# BMS_Communications.net
KiCad netlist of a schematic drawn in Altium Designer
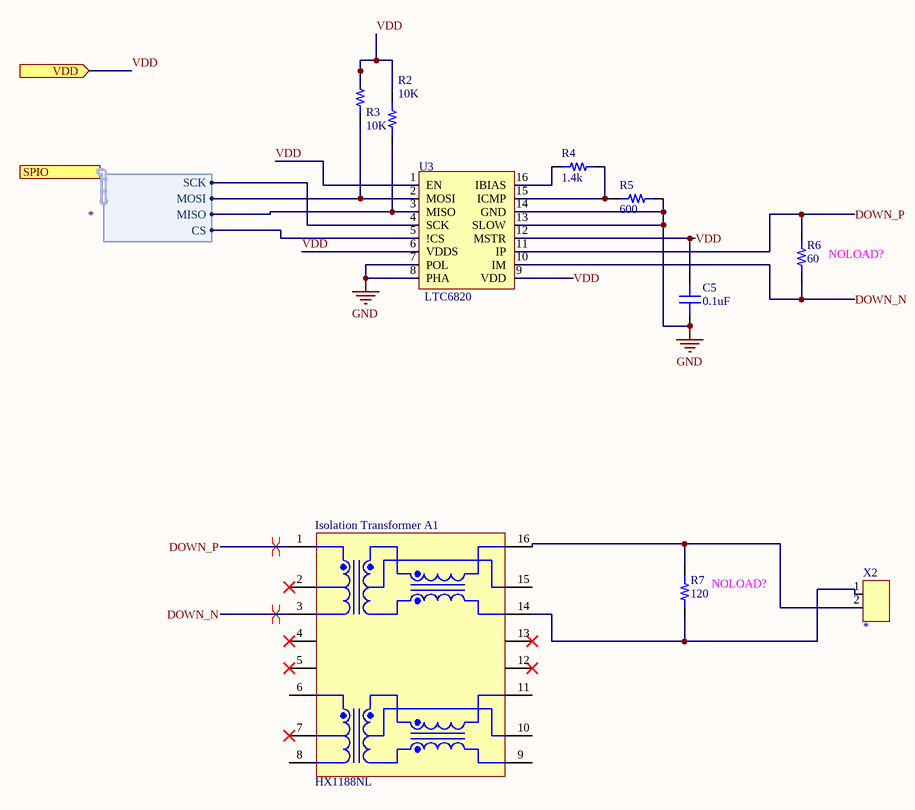
[diagram p0: BMS Communications.SchDoc]

(export (version "E")
  (design (tool "Eeschema 10.0.6"))
  (components
    (comp (ref "C5")
      (value "capacitor")
      (footprint "0603")
      (description "Generic 0603 capacitor")
      (fields (field (name "CAPACITANCE") "0.1uF") (field (name "VOLTAGE") "50"))
      (libsource (lib "altlib") (part "capacitor"))
    )
    (comp (ref "Isolation Transformer A1")
      (value "HX1188NL")
      (footprint "PULS-MODULE-16_V")
      (fields (field (name "MANUFACTURER") "Pulse Electronics"))
      (libsource (lib "Altium Content Vault") (part "PULS-HX1188NL-MODULE-16"))
    )
    (comp (ref "R2")
      (value "10K")
      (footprint "RES 0603/1608")
      (fields (field (name "RESISTANCE") "10K"))
      (libsource (lib "altlib") (part "Resistor"))
    )
    (comp (ref "R3")
      (value "10K")
      (footprint "RES 0603/1608")
      (fields (field (name "RESISTANCE") "10K"))
      (libsource (lib "altlib") (part "Resistor"))
    )
    (comp (ref "R4")
      (value "1.4k")
      (footprint "RES 0603/1608")
      (fields (field (name "RESISTANCE") "1.4k"))
      (libsource (lib "altlib") (part "Resistor"))
    )
    (comp (ref "R5")
      (value "600")
      (footprint "RES 0603/1608")
      (fields (field (name "RESISTANCE") "600"))
      (libsource (lib "altlib") (part "Resistor"))
    )
    (comp (ref "R6")
      (value "60")
      (footprint "RES 0603/1608")
      (fields (field (name "RESISTANCE") "60"))
      (libsource (lib "altlib") (part "Resistor"))
    )
    (comp (ref "R7")
      (value "120")
      (footprint "RES 0603/1608")
      (fields (field (name "RESISTANCE") "120"))
      (libsource (lib "altlib") (part "Resistor"))
    )
    (comp (ref "U3")
      (value "LTC6820")
      (footprint "MSOP-16")
      (description "soSPI Isolated\nCommunications Interface")
      (libsource (lib "altlib") (part "LTC6820"))
    )
    (comp (ref "X2")
      (value "*")
      (footprint "CONN 43650-0200 MOLEX 2PIN")
      (description "Molex 43650_0200")
      (libsource (lib "altlib") (part "CONN 2POS"))
    )
  )
  (nets
    (net (code "2") (name "/CS") (class "Default")
      (node (ref "U3") (pin "5") (pinfunction "!CS_5") (pintype "input"))
    )
    (net (code "3") (name "/DOWN_N") (class "Default")
      (node (ref "Isolation Transformer A1") (pin "3") (pinfunction "3_3") (pintype "passive"))
      (node (ref "R6") (pin "1") (pinfunction "1_1") (pintype "passive"))
      (node (ref "U3") (pin "10") (pinfunction "IM_10") (pintype "input"))
    )
    (net (code "4") (name "/DOWN_P") (class "Default")
      (node (ref "Isolation Transformer A1") (pin "1") (pinfunction "1_1") (pintype "passive"))
      (node (ref "R6") (pin "2") (pinfunction "2_2") (pintype "passive"))
      (node (ref "U3") (pin "11") (pinfunction "IP_11") (pintype "input"))
    )
    (net (code "5") (name "/MISO") (class "Default")
      (node (ref "R2") (pin "1") (pinfunction "1_1") (pintype "passive"))
      (node (ref "U3") (pin "3") (pinfunction "MISO_3") (pintype "input"))
    )
    (net (code "6") (name "/MOSI") (class "Default")
      (node (ref "R3") (pin "2") (pinfunction "2_2") (pintype "passive"))
      (node (ref "U3") (pin "2") (pinfunction "MOSI_2") (pintype "input"))
    )
    (net (code "7") (name "/SCK") (class "Default")
      (node (ref "U3") (pin "4") (pinfunction "SCK_4") (pintype "input"))
    )
    (net (code "8") (name "/VDD") (class "Default")
      (node (ref "C5") (pin "2") (pinfunction "2_2") (pintype "passive"))
      (node (ref "R2") (pin "2") (pinfunction "2_2") (pintype "passive"))
      (node (ref "R3") (pin "1") (pinfunction "1_1") (pintype "passive"))
      (node (ref "U3") (pin "1") (pinfunction "EN_1") (pintype "input"))
      (node (ref "U3") (pin "12") (pinfunction "MSTR_12") (pintype "input"))
      (node (ref "U3") (pin "6") (pinfunction "VDDS_6") (pintype "input"))
      (node (ref "U3") (pin "9") (pinfunction "VDD_9") (pintype "input"))
    )
    (net (code "10") (name "GND") (class "Default")
      (node (ref "C5") (pin "1") (pinfunction "1_1") (pintype "passive"))
      (node (ref "R5") (pin "1") (pinfunction "1_1") (pintype "passive"))
      (node (ref "U3") (pin "13") (pinfunction "SLOW_13") (pintype "input"))
      (node (ref "U3") (pin "14") (pinfunction "GND_14") (pintype "input"))
      (node (ref "U3") (pin "7") (pinfunction "POL_7") (pintype "input"))
      (node (ref "U3") (pin "8") (pinfunction "PHA_8") (pintype "input"))
    )
    (net (code "11") (name "Net-(Isolation Transformer A1-Pad14)") (class "Default")
      (node (ref "Isolation Transformer A1") (pin "14") (pinfunction "14_14") (pintype "passive"))
      (node (ref "R7") (pin "1") (pinfunction "1_1") (pintype "passive"))
      (node (ref "X2") (pin "1") (pintype "passive"))
    )
    (net (code "12") (name "Net-(Isolation Transformer A1-Pad16)") (class "Default")
      (node (ref "Isolation Transformer A1") (pin "16") (pinfunction "16_16") (pintype "passive"))
      (node (ref "R7") (pin "2") (pinfunction "2_2") (pintype "passive"))
      (node (ref "X2") (pin "2") (pintype "passive"))
    )
    (net (code "13") (name "Net-(U3-IBIAS)") (class "Default")
      (node (ref "R4") (pin "2") (pinfunction "2_2") (pintype "passive"))
      (node (ref "U3") (pin "16") (pinfunction "IBIAS_16") (pintype "input"))
    )
    (net (code "14") (name "Net-(U3-ICMP)") (class "Default")
      (node (ref "R4") (pin "1") (pinfunction "1_1") (pintype "passive"))
      (node (ref "R5") (pin "2") (pinfunction "2_2") (pintype "passive"))
      (node (ref "U3") (pin "15") (pinfunction "ICMP_15") (pintype "input"))
    )
    (net (code "15") (name "unconnected-(Isolation Transformer A1-Pad2)") (class "Default")
      (node (ref "Isolation Transformer A1") (pin "2") (pinfunction "2_2") (pintype "passive+no_connect"))
    )
    (net (code "16") (name "unconnected-(Isolation Transformer A1-Pad4)") (class "Default")
      (node (ref "Isolation Transformer A1") (pin "4") (pinfunction "4_4") (pintype "passive+no_connect"))
    )
    (net (code "17") (name "unconnected-(Isolation Transformer A1-Pad5)") (class "Default")
      (node (ref "Isolation Transformer A1") (pin "5") (pinfunction "5_5") (pintype "passive+no_connect"))
    )
    (net (code "18") (name "unconnected-(Isolation Transformer A1-Pad6)") (class "Default")
      (node (ref "Isolation Transformer A1") (pin "6") (pinfunction "6_6") (pintype "passive"))
    )
    (net (code "19") (name "unconnected-(Isolation Transformer A1-Pad7)") (class "Default")
      (node (ref "Isolation Transformer A1") (pin "7") (pinfunction "7_7") (pintype "passive+no_connect"))
    )
    (net (code "20") (name "unconnected-(Isolation Transformer A1-Pad8)") (class "Default")
      (node (ref "Isolation Transformer A1") (pin "8") (pinfunction "8_8") (pintype "passive"))
    )
    (net (code "21") (name "unconnected-(Isolation Transformer A1-Pad9)") (class "Default")
      (node (ref "Isolation Transformer A1") (pin "9") (pinfunction "9_9") (pintype "passive"))
    )
    (net (code "22") (name "unconnected-(Isolation Transformer A1-Pad10)") (class "Default")
      (node (ref "Isolation Transformer A1") (pin "10") (pinfunction "10_10") (pintype "passive"))
    )
    (net (code "23") (name "unconnected-(Isolation Transformer A1-Pad11)") (class "Default")
      (node (ref "Isolation Transformer A1") (pin "11") (pinfunction "11_11") (pintype "passive"))
    )
    (net (code "24") (name "unconnected-(Isolation Transformer A1-Pad12)") (class "Default")
      (node (ref "Isolation Transformer A1") (pin "12") (pinfunction "12_12") (pintype "passive+no_connect"))
    )
    (net (code "25") (name "unconnected-(Isolation Transformer A1-Pad13)") (class "Default")
      (node (ref "Isolation Transformer A1") (pin "13") (pinfunction "13_13") (pintype "passive+no_connect"))
    )
    (net (code "26") (name "unconnected-(Isolation Transformer A1-Pad15)") (class "Default")
      (node (ref "Isolation Transformer A1") (pin "15") (pinfunction "15_15") (pintype "passive"))
    )
  )
)
